# vpcb.net
KiCad netlist of a schematic drawn in EAGLE
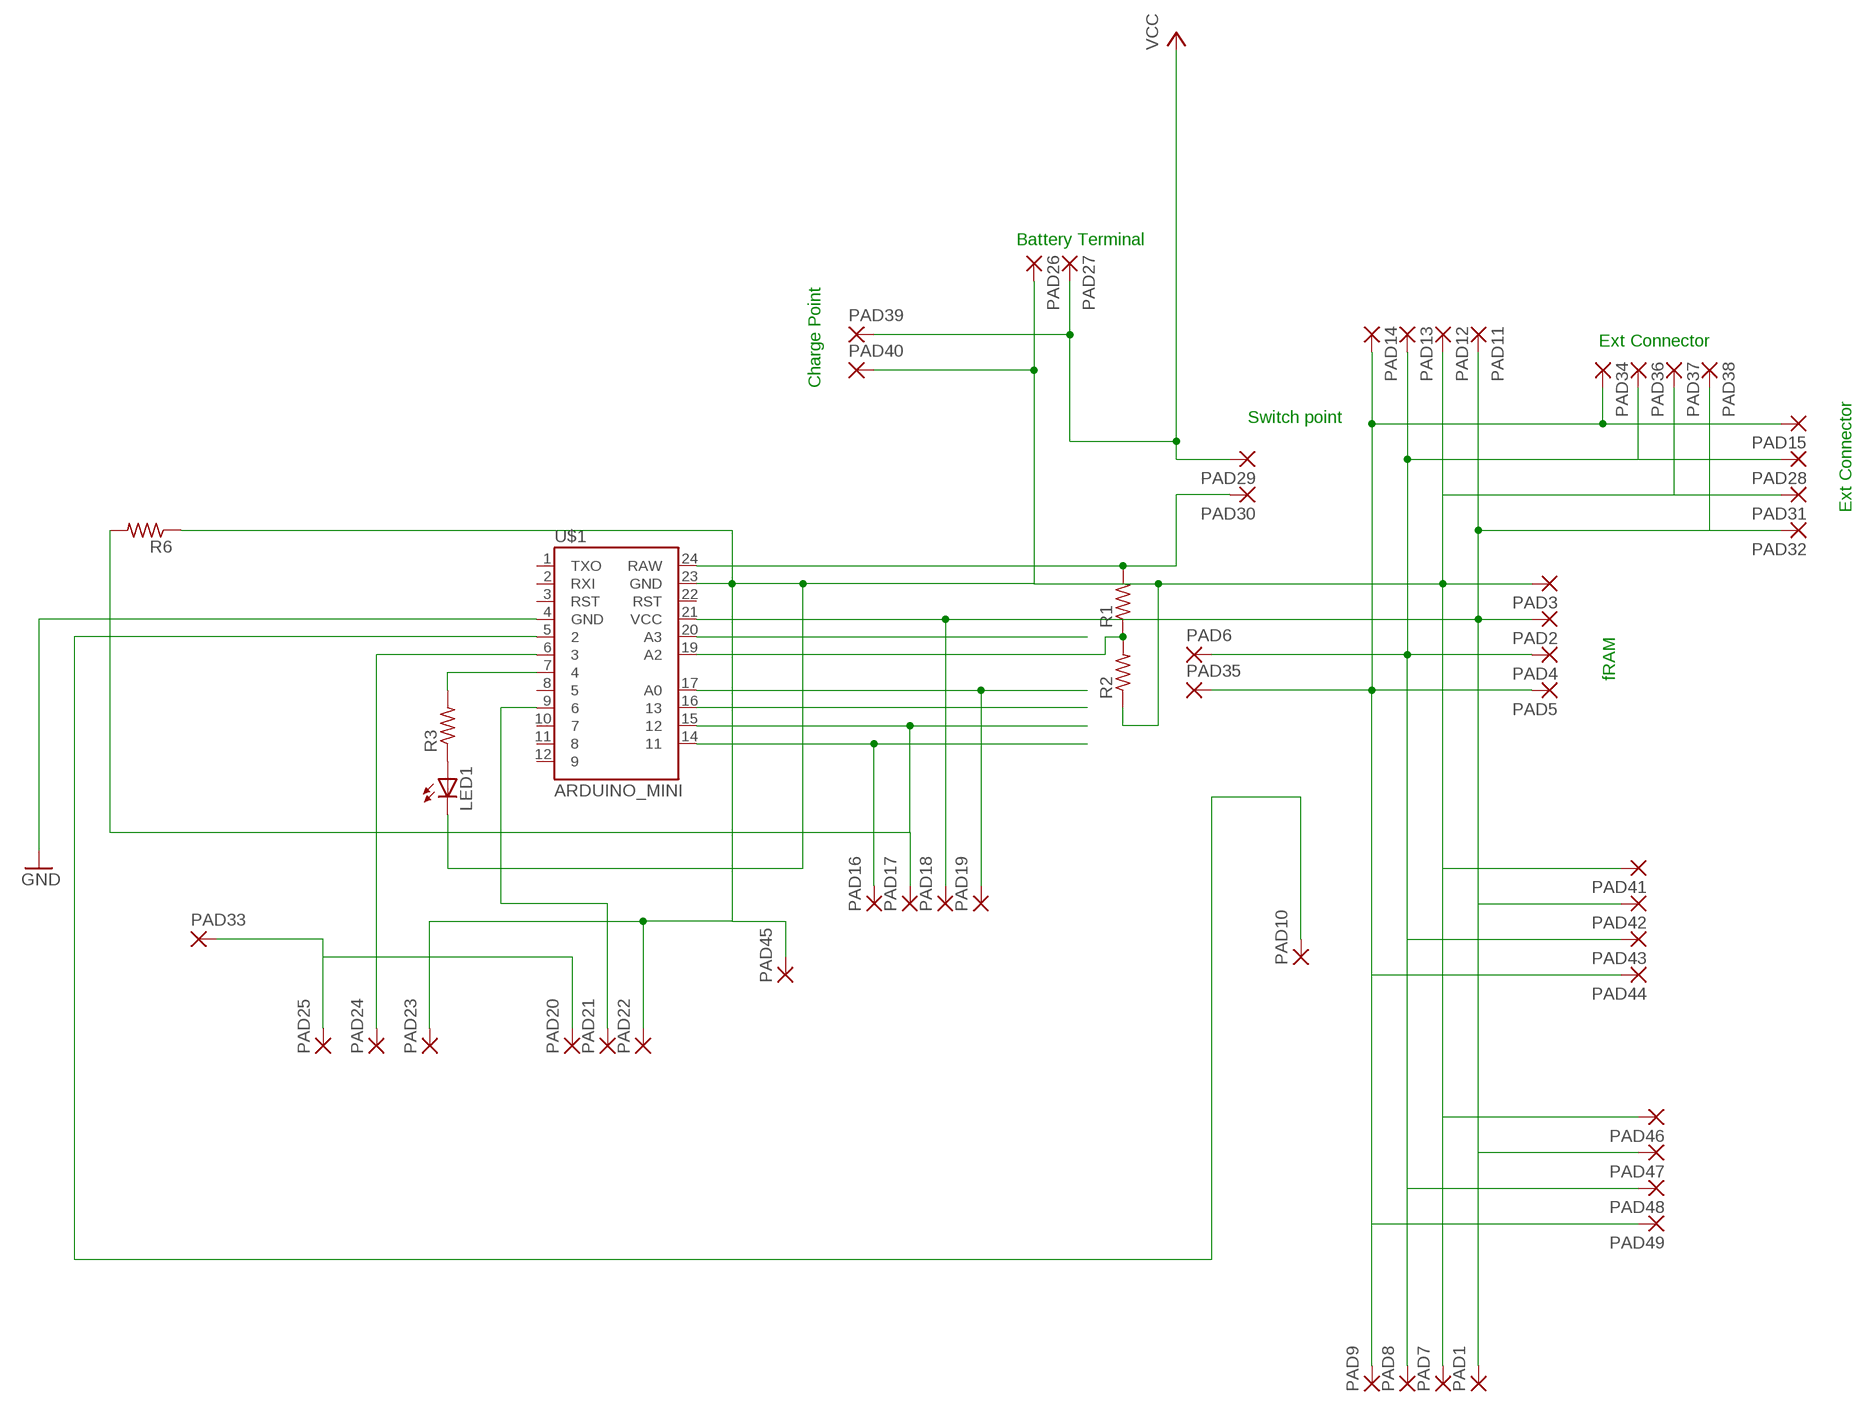
[diagram p0: schematic, sheet 1]

(export (version "E")
  (design (tool "Eeschema 10.0.6"))
  (components
    (comp (ref "LED1")
      (value "LED3MM")
      (footprint "eagle-import:LED3MM")
      (libsource (lib "eagle-import") (part "LED3MM"))
    )
    (comp (ref "PAD1")
      (value "2,15/1,0")
      (footprint "eagle-import:2,15_1,0")
      (libsource (lib "eagle-import") (part "2,15/1,0"))
    )
    (comp (ref "PAD2")
      (value "2,15/1,0")
      (footprint "eagle-import:2,15_1,0")
      (libsource (lib "eagle-import") (part "2,15/1,0"))
    )
    (comp (ref "PAD3")
      (value "2,15/1,0")
      (footprint "eagle-import:2,15_1,0")
      (libsource (lib "eagle-import") (part "2,15/1,0"))
    )
    (comp (ref "PAD4")
      (value "2,15/1,0")
      (footprint "eagle-import:2,15_1,0")
      (libsource (lib "eagle-import") (part "2,15/1,0"))
    )
    (comp (ref "PAD5")
      (value "2,15/1,0")
      (footprint "eagle-import:2,15_1,0")
      (libsource (lib "eagle-import") (part "2,15/1,0"))
    )
    (comp (ref "PAD6")
      (value "2,15/1,0")
      (footprint "eagle-import:2,15_1,0")
      (libsource (lib "eagle-import") (part "2,15/1,0"))
    )
    (comp (ref "PAD7")
      (value "2,15/1,0")
      (footprint "eagle-import:2,15_1,0")
      (libsource (lib "eagle-import") (part "2,15/1,0"))
    )
    (comp (ref "PAD8")
      (value "2,15/1,0")
      (footprint "eagle-import:2,15_1,0")
      (libsource (lib "eagle-import") (part "2,15/1,0"))
    )
    (comp (ref "PAD9")
      (value "2,15/1,0")
      (footprint "eagle-import:2,15_1,0")
      (libsource (lib "eagle-import") (part "2,15/1,0"))
    )
    (comp (ref "PAD10")
      (value "2,15/1,0")
      (footprint "eagle-import:2,15_1,0")
      (libsource (lib "eagle-import") (part "2,15/1,0"))
    )
    (comp (ref "PAD11")
      (value "2,15/1,0")
      (footprint "eagle-import:2,15_1,0")
      (libsource (lib "eagle-import") (part "2,15/1,0"))
    )
    (comp (ref "PAD12")
      (value "2,15/1,0")
      (footprint "eagle-import:2,15_1,0")
      (libsource (lib "eagle-import") (part "2,15/1,0"))
    )
    (comp (ref "PAD13")
      (value "2,15/1,0")
      (footprint "eagle-import:2,15_1,0")
      (libsource (lib "eagle-import") (part "2,15/1,0"))
    )
    (comp (ref "PAD14")
      (value "2,15/1,0")
      (footprint "eagle-import:2,15_1,0")
      (libsource (lib "eagle-import") (part "2,15/1,0"))
    )
    (comp (ref "PAD15")
      (value "2,15/1,0")
      (footprint "eagle-import:2,15_1,0")
      (libsource (lib "eagle-import") (part "2,15/1,0"))
    )
    (comp (ref "PAD16")
      (value "2,15/1,0")
      (footprint "eagle-import:2,15_1,0")
      (libsource (lib "eagle-import") (part "2,15/1,0"))
    )
    (comp (ref "PAD17")
      (value "2,15/1,0")
      (footprint "eagle-import:2,15_1,0")
      (libsource (lib "eagle-import") (part "2,15/1,0"))
    )
    (comp (ref "PAD18")
      (value "2,15/1,0")
      (footprint "eagle-import:2,15_1,0")
      (libsource (lib "eagle-import") (part "2,15/1,0"))
    )
    (comp (ref "PAD19")
      (value "2,15/1,0")
      (footprint "eagle-import:2,15_1,0")
      (libsource (lib "eagle-import") (part "2,15/1,0"))
    )
    (comp (ref "PAD20")
      (value "2,15/1,0")
      (footprint "eagle-import:2,15_1,0")
      (libsource (lib "eagle-import") (part "2,15/1,0"))
    )
    (comp (ref "PAD21")
      (value "2,15/1,0")
      (footprint "eagle-import:2,15_1,0")
      (libsource (lib "eagle-import") (part "2,15/1,0"))
    )
    (comp (ref "PAD22")
      (value "2,15/1,0")
      (footprint "eagle-import:2,15_1,0")
      (libsource (lib "eagle-import") (part "2,15/1,0"))
    )
    (comp (ref "PAD23")
      (value "2,15/1,0")
      (footprint "eagle-import:2,15_1,0")
      (libsource (lib "eagle-import") (part "2,15/1,0"))
    )
    (comp (ref "PAD24")
      (value "2,15/1,0")
      (footprint "eagle-import:2,15_1,0")
      (libsource (lib "eagle-import") (part "2,15/1,0"))
    )
    (comp (ref "PAD25")
      (value "2,15/1,0")
      (footprint "eagle-import:2,15_1,0")
      (libsource (lib "eagle-import") (part "2,15/1,0"))
    )
    (comp (ref "PAD26")
      (value "2,15/1,0")
      (footprint "eagle-import:2,15_1,0")
      (libsource (lib "eagle-import") (part "2,15/1,0"))
    )
    (comp (ref "PAD27")
      (value "2,15/1,0")
      (footprint "eagle-import:2,15_1,0")
      (libsource (lib "eagle-import") (part "2,15/1,0"))
    )
    (comp (ref "PAD28")
      (value "2,15/1,0")
      (footprint "eagle-import:2,15_1,0")
      (libsource (lib "eagle-import") (part "2,15/1,0"))
    )
    (comp (ref "PAD29")
      (value "2,15/1,0")
      (footprint "eagle-import:2,15_1,0")
      (libsource (lib "eagle-import") (part "2,15/1,0"))
    )
    (comp (ref "PAD30")
      (value "2,15/1,0")
      (footprint "eagle-import:2,15_1,0")
      (libsource (lib "eagle-import") (part "2,15/1,0"))
    )
    (comp (ref "PAD31")
      (value "2,15/1,0")
      (footprint "eagle-import:2,15_1,0")
      (libsource (lib "eagle-import") (part "2,15/1,0"))
    )
    (comp (ref "PAD32")
      (value "2,15/1,0")
      (footprint "eagle-import:2,15_1,0")
      (libsource (lib "eagle-import") (part "2,15/1,0"))
    )
    (comp (ref "PAD33")
      (value "2,15/1,0")
      (footprint "eagle-import:2,15_1,0")
      (libsource (lib "eagle-import") (part "2,15/1,0"))
    )
    (comp (ref "PAD34")
      (value "2,15/1,0")
      (footprint "eagle-import:2,15_1,0")
      (libsource (lib "eagle-import") (part "2,15/1,0"))
    )
    (comp (ref "PAD35")
      (value "2,15/1,0")
      (footprint "eagle-import:2,15_1,0")
      (libsource (lib "eagle-import") (part "2,15/1,0"))
    )
    (comp (ref "PAD36")
      (value "2,15/1,0")
      (footprint "eagle-import:2,15_1,0")
      (libsource (lib "eagle-import") (part "2,15/1,0"))
    )
    (comp (ref "PAD37")
      (value "2,15/1,0")
      (footprint "eagle-import:2,15_1,0")
      (libsource (lib "eagle-import") (part "2,15/1,0"))
    )
    (comp (ref "PAD38")
      (value "2,15/1,0")
      (footprint "eagle-import:2,15_1,0")
      (libsource (lib "eagle-import") (part "2,15/1,0"))
    )
    (comp (ref "PAD39")
      (value "2,15/1,0")
      (footprint "eagle-import:2,15_1,0")
      (libsource (lib "eagle-import") (part "2,15/1,0"))
    )
    (comp (ref "PAD40")
      (value "2,15/1,0")
      (footprint "eagle-import:2,15_1,0")
      (libsource (lib "eagle-import") (part "2,15/1,0"))
    )
    (comp (ref "PAD41")
      (value "2,15/1,0")
      (footprint "eagle-import:2,15_1,0")
      (libsource (lib "eagle-import") (part "2,15/1,0"))
    )
    (comp (ref "PAD42")
      (value "2,15/1,0")
      (footprint "eagle-import:2,15_1,0")
      (libsource (lib "eagle-import") (part "2,15/1,0"))
    )
    (comp (ref "PAD43")
      (value "2,15/1,0")
      (footprint "eagle-import:2,15_1,0")
      (libsource (lib "eagle-import") (part "2,15/1,0"))
    )
    (comp (ref "PAD44")
      (value "2,15/1,0")
      (footprint "eagle-import:2,15_1,0")
      (libsource (lib "eagle-import") (part "2,15/1,0"))
    )
    (comp (ref "PAD45")
      (value "2,15/1,0")
      (footprint "eagle-import:2,15_1,0")
      (libsource (lib "eagle-import") (part "2,15/1,0"))
    )
    (comp (ref "PAD46")
      (value "2,15/1,0")
      (footprint "eagle-import:2,15_1,0")
      (libsource (lib "eagle-import") (part "2,15/1,0"))
    )
    (comp (ref "PAD47")
      (value "2,15/1,0")
      (footprint "eagle-import:2,15_1,0")
      (libsource (lib "eagle-import") (part "2,15/1,0"))
    )
    (comp (ref "PAD48")
      (value "2,15/1,0")
      (footprint "eagle-import:2,15_1,0")
      (libsource (lib "eagle-import") (part "2,15/1,0"))
    )
    (comp (ref "PAD49")
      (value "2,15/1,0")
      (footprint "eagle-import:2,15_1,0")
      (libsource (lib "eagle-import") (part "2,15/1,0"))
    )
    (comp (ref "R1")
      (value "R-US_0204/7")
      (footprint "eagle-import:0204_7")
      (libsource (lib "eagle-import") (part "resistor_R-US_0204/7"))
    )
    (comp (ref "R2")
      (value "R-US_0204/7")
      (footprint "eagle-import:0204_7")
      (libsource (lib "eagle-import") (part "resistor_R-US_0204/7"))
    )
    (comp (ref "R3")
      (value "R-US_0204/7")
      (footprint "eagle-import:0204_7")
      (libsource (lib "eagle-import") (part "resistor_R-US_0204/7"))
    )
    (comp (ref "R6")
      (value "R-US_0204/5")
      (footprint "eagle-import:0204_5")
      (libsource (lib "eagle-import") (part "R-US_0204/5"))
    )
    (comp (ref "U$1")
      (value "ARDUINO_MINI")
      (footprint "eagle-import:ARDUINO_MINI")
      (libsource (lib "eagle-import") (part "ARDUINO_MINI"))
    )
  )
  (nets
    (net (code "1") (name "GND") (class "Default")
      (node (ref "U$1") (pin "4") (pinfunction "GND_4") (pintype "bidirectional"))
    )
    (net (code "2") (name "Net-(LED1-C)") (class "Default")
      (node (ref "LED1") (pin "K") (pinfunction "C_K") (pintype "passive"))
      (node (ref "PAD12") (pin "1") (pinfunction "P_1") (pintype "passive"))
      (node (ref "PAD22") (pin "1") (pinfunction "P_1") (pintype "passive"))
      (node (ref "PAD23") (pin "1") (pinfunction "P_1") (pintype "passive"))
      (node (ref "PAD26") (pin "1") (pinfunction "P_1") (pintype "passive"))
      (node (ref "PAD3") (pin "1") (pinfunction "P_1") (pintype "passive"))
      (node (ref "PAD31") (pin "1") (pinfunction "P_1") (pintype "passive"))
      (node (ref "PAD37") (pin "1") (pinfunction "P_1") (pintype "passive"))
      (node (ref "PAD40") (pin "1") (pinfunction "P_1") (pintype "passive"))
      (node (ref "PAD41") (pin "1") (pinfunction "P_1") (pintype "passive"))
      (node (ref "PAD45") (pin "1") (pinfunction "P_1") (pintype "passive"))
      (node (ref "PAD46") (pin "1") (pinfunction "P_1") (pintype "passive"))
      (node (ref "PAD7") (pin "1") (pinfunction "P_1") (pintype "passive"))
      (node (ref "R2") (pin "1") (pinfunction "1_1") (pintype "passive"))
      (node (ref "R6") (pin "1") (pinfunction "1_1") (pintype "passive"))
      (node (ref "U$1") (pin "23") (pinfunction "GND_23") (pintype "bidirectional"))
    )
    (net (code "3") (name "Net-(LED1-PadA)") (class "Default")
      (node (ref "LED1") (pin "A") (pinfunction "A_A") (pintype "passive"))
      (node (ref "R3") (pin "1") (pinfunction "1_1") (pintype "passive"))
    )
    (net (code "4") (name "Net-(PAD1-P)") (class "Default")
      (node (ref "PAD1") (pin "1") (pinfunction "P_1") (pintype "passive"))
      (node (ref "PAD11") (pin "1") (pinfunction "P_1") (pintype "passive"))
      (node (ref "PAD18") (pin "1") (pinfunction "P_1") (pintype "passive"))
      (node (ref "PAD2") (pin "1") (pinfunction "P_1") (pintype "passive"))
      (node (ref "PAD32") (pin "1") (pinfunction "P_1") (pintype "passive"))
      (node (ref "PAD38") (pin "1") (pinfunction "P_1") (pintype "passive"))
      (node (ref "PAD42") (pin "1") (pinfunction "P_1") (pintype "passive"))
      (node (ref "PAD47") (pin "1") (pinfunction "P_1") (pintype "passive"))
      (node (ref "U$1") (pin "21") (pinfunction "VCC_21") (pintype "bidirectional"))
    )
    (net (code "5") (name "Net-(PAD10-P)") (class "Default")
      (node (ref "PAD10") (pin "1") (pinfunction "P_1") (pintype "passive"))
      (node (ref "U$1") (pin "5") (pinfunction "2_5") (pintype "bidirectional"))
    )
    (net (code "6") (name "Net-(PAD13-P)") (class "Default")
      (node (ref "PAD13") (pin "1") (pinfunction "P_1") (pintype "passive"))
      (node (ref "PAD28") (pin "1") (pinfunction "P_1") (pintype "passive"))
      (node (ref "PAD36") (pin "1") (pinfunction "P_1") (pintype "passive"))
      (node (ref "PAD4") (pin "1") (pinfunction "P_1") (pintype "passive"))
      (node (ref "PAD43") (pin "1") (pinfunction "P_1") (pintype "passive"))
      (node (ref "PAD48") (pin "1") (pinfunction "P_1") (pintype "passive"))
      (node (ref "PAD6") (pin "1") (pinfunction "P_1") (pintype "passive"))
      (node (ref "PAD8") (pin "1") (pinfunction "P_1") (pintype "passive"))
    )
    (net (code "7") (name "Net-(PAD14-P)") (class "Default")
      (node (ref "PAD14") (pin "1") (pinfunction "P_1") (pintype "passive"))
      (node (ref "PAD15") (pin "1") (pinfunction "P_1") (pintype "passive"))
      (node (ref "PAD34") (pin "1") (pinfunction "P_1") (pintype "passive"))
      (node (ref "PAD35") (pin "1") (pinfunction "P_1") (pintype "passive"))
      (node (ref "PAD44") (pin "1") (pinfunction "P_1") (pintype "passive"))
      (node (ref "PAD49") (pin "1") (pinfunction "P_1") (pintype "passive"))
      (node (ref "PAD5") (pin "1") (pinfunction "P_1") (pintype "passive"))
      (node (ref "PAD9") (pin "1") (pinfunction "P_1") (pintype "passive"))
    )
    (net (code "8") (name "Net-(PAD16-P)") (class "Default")
      (node (ref "PAD16") (pin "1") (pinfunction "P_1") (pintype "passive"))
      (node (ref "U$1") (pin "14") (pinfunction "11_14") (pintype "bidirectional"))
    )
    (net (code "9") (name "Net-(PAD17-P)") (class "Default")
      (node (ref "PAD17") (pin "1") (pinfunction "P_1") (pintype "passive"))
      (node (ref "R6") (pin "2") (pinfunction "2_2") (pintype "passive"))
      (node (ref "U$1") (pin "15") (pinfunction "12_15") (pintype "bidirectional"))
    )
    (net (code "10") (name "Net-(PAD19-P)") (class "Default")
      (node (ref "PAD19") (pin "1") (pinfunction "P_1") (pintype "passive"))
      (node (ref "U$1") (pin "17") (pinfunction "A0_17") (pintype "bidirectional"))
    )
    (net (code "11") (name "Net-(PAD20-P)") (class "Default")
      (node (ref "PAD20") (pin "1") (pinfunction "P_1") (pintype "passive"))
      (node (ref "PAD25") (pin "1") (pinfunction "P_1") (pintype "passive"))
      (node (ref "PAD33") (pin "1") (pinfunction "P_1") (pintype "passive"))
    )
    (net (code "12") (name "Net-(PAD21-P)") (class "Default")
      (node (ref "PAD21") (pin "1") (pinfunction "P_1") (pintype "passive"))
      (node (ref "U$1") (pin "9") (pinfunction "6_9") (pintype "bidirectional"))
    )
    (net (code "13") (name "Net-(PAD24-P)") (class "Default")
      (node (ref "PAD24") (pin "1") (pinfunction "P_1") (pintype "passive"))
      (node (ref "U$1") (pin "6") (pinfunction "3_6") (pintype "bidirectional"))
    )
    (net (code "14") (name "Net-(PAD30-P)") (class "Default")
      (node (ref "PAD30") (pin "1") (pinfunction "P_1") (pintype "passive"))
      (node (ref "R1") (pin "2") (pinfunction "2_2") (pintype "passive"))
      (node (ref "U$1") (pin "24") (pinfunction "RAW_24") (pintype "bidirectional"))
    )
    (net (code "15") (name "Net-(U$1-4)") (class "Default")
      (node (ref "R3") (pin "2") (pinfunction "2_2") (pintype "passive"))
      (node (ref "U$1") (pin "7") (pinfunction "4_7") (pintype "bidirectional"))
    )
    (net (code "16") (name "Net-(U$1-A2)") (class "Default")
      (node (ref "R1") (pin "1") (pinfunction "1_1") (pintype "passive"))
      (node (ref "R2") (pin "2") (pinfunction "2_2") (pintype "passive"))
      (node (ref "U$1") (pin "19") (pinfunction "A2_19") (pintype "bidirectional"))
    )
    (net (code "17") (name "VCC") (class "Default")
      (node (ref "PAD27") (pin "1") (pinfunction "P_1") (pintype "passive"))
      (node (ref "PAD29") (pin "1") (pinfunction "P_1") (pintype "passive"))
      (node (ref "PAD39") (pin "1") (pinfunction "P_1") (pintype "passive"))
    )
    (net (code "18") (name "unconnected-(U$1-5-Pad8)") (class "Default")
      (node (ref "U$1") (pin "8") (pinfunction "5_8") (pintype "bidirectional"))
    )
    (net (code "19") (name "unconnected-(U$1-7-Pad10)") (class "Default")
      (node (ref "U$1") (pin "10") (pinfunction "7_10") (pintype "bidirectional"))
    )
    (net (code "20") (name "unconnected-(U$1-8-Pad11)") (class "Default")
      (node (ref "U$1") (pin "11") (pinfunction "8_11") (pintype "bidirectional"))
    )
    (net (code "21") (name "unconnected-(U$1-9-Pad12)") (class "Default")
      (node (ref "U$1") (pin "12") (pinfunction "9_12") (pintype "bidirectional"))
    )
    (net (code "22") (name "unconnected-(U$1-13-Pad16)") (class "Default")
      (node (ref "U$1") (pin "16") (pinfunction "13_16") (pintype "bidirectional"))
    )
    (net (code "23") (name "unconnected-(U$1-A3-Pad20)") (class "Default")
      (node (ref "U$1") (pin "20") (pinfunction "A3_20") (pintype "bidirectional"))
    )
    (net (code "24") (name "unconnected-(U$1-RST-Pad3)") (class "Default")
      (node (ref "U$1") (pin "3") (pinfunction "RST_3") (pintype "bidirectional"))
    )
    (net (code "25") (name "unconnected-(U$1-RST-Pad22)") (class "Default")
      (node (ref "U$1") (pin "22") (pinfunction "RST_22") (pintype "bidirectional"))
    )
    (net (code "26") (name "unconnected-(U$1-RXI-Pad2)") (class "Default")
      (node (ref "U$1") (pin "2") (pinfunction "RXI_2") (pintype "bidirectional"))
    )
    (net (code "27") (name "unconnected-(U$1-TXO-Pad1)") (class "Default")
      (node (ref "U$1") (pin "1") (pinfunction "TXO_1") (pintype "bidirectional"))
    )
  )
)
